# main-board_v1_3.net
KiCad netlist of a schematic drawn in EAGLE
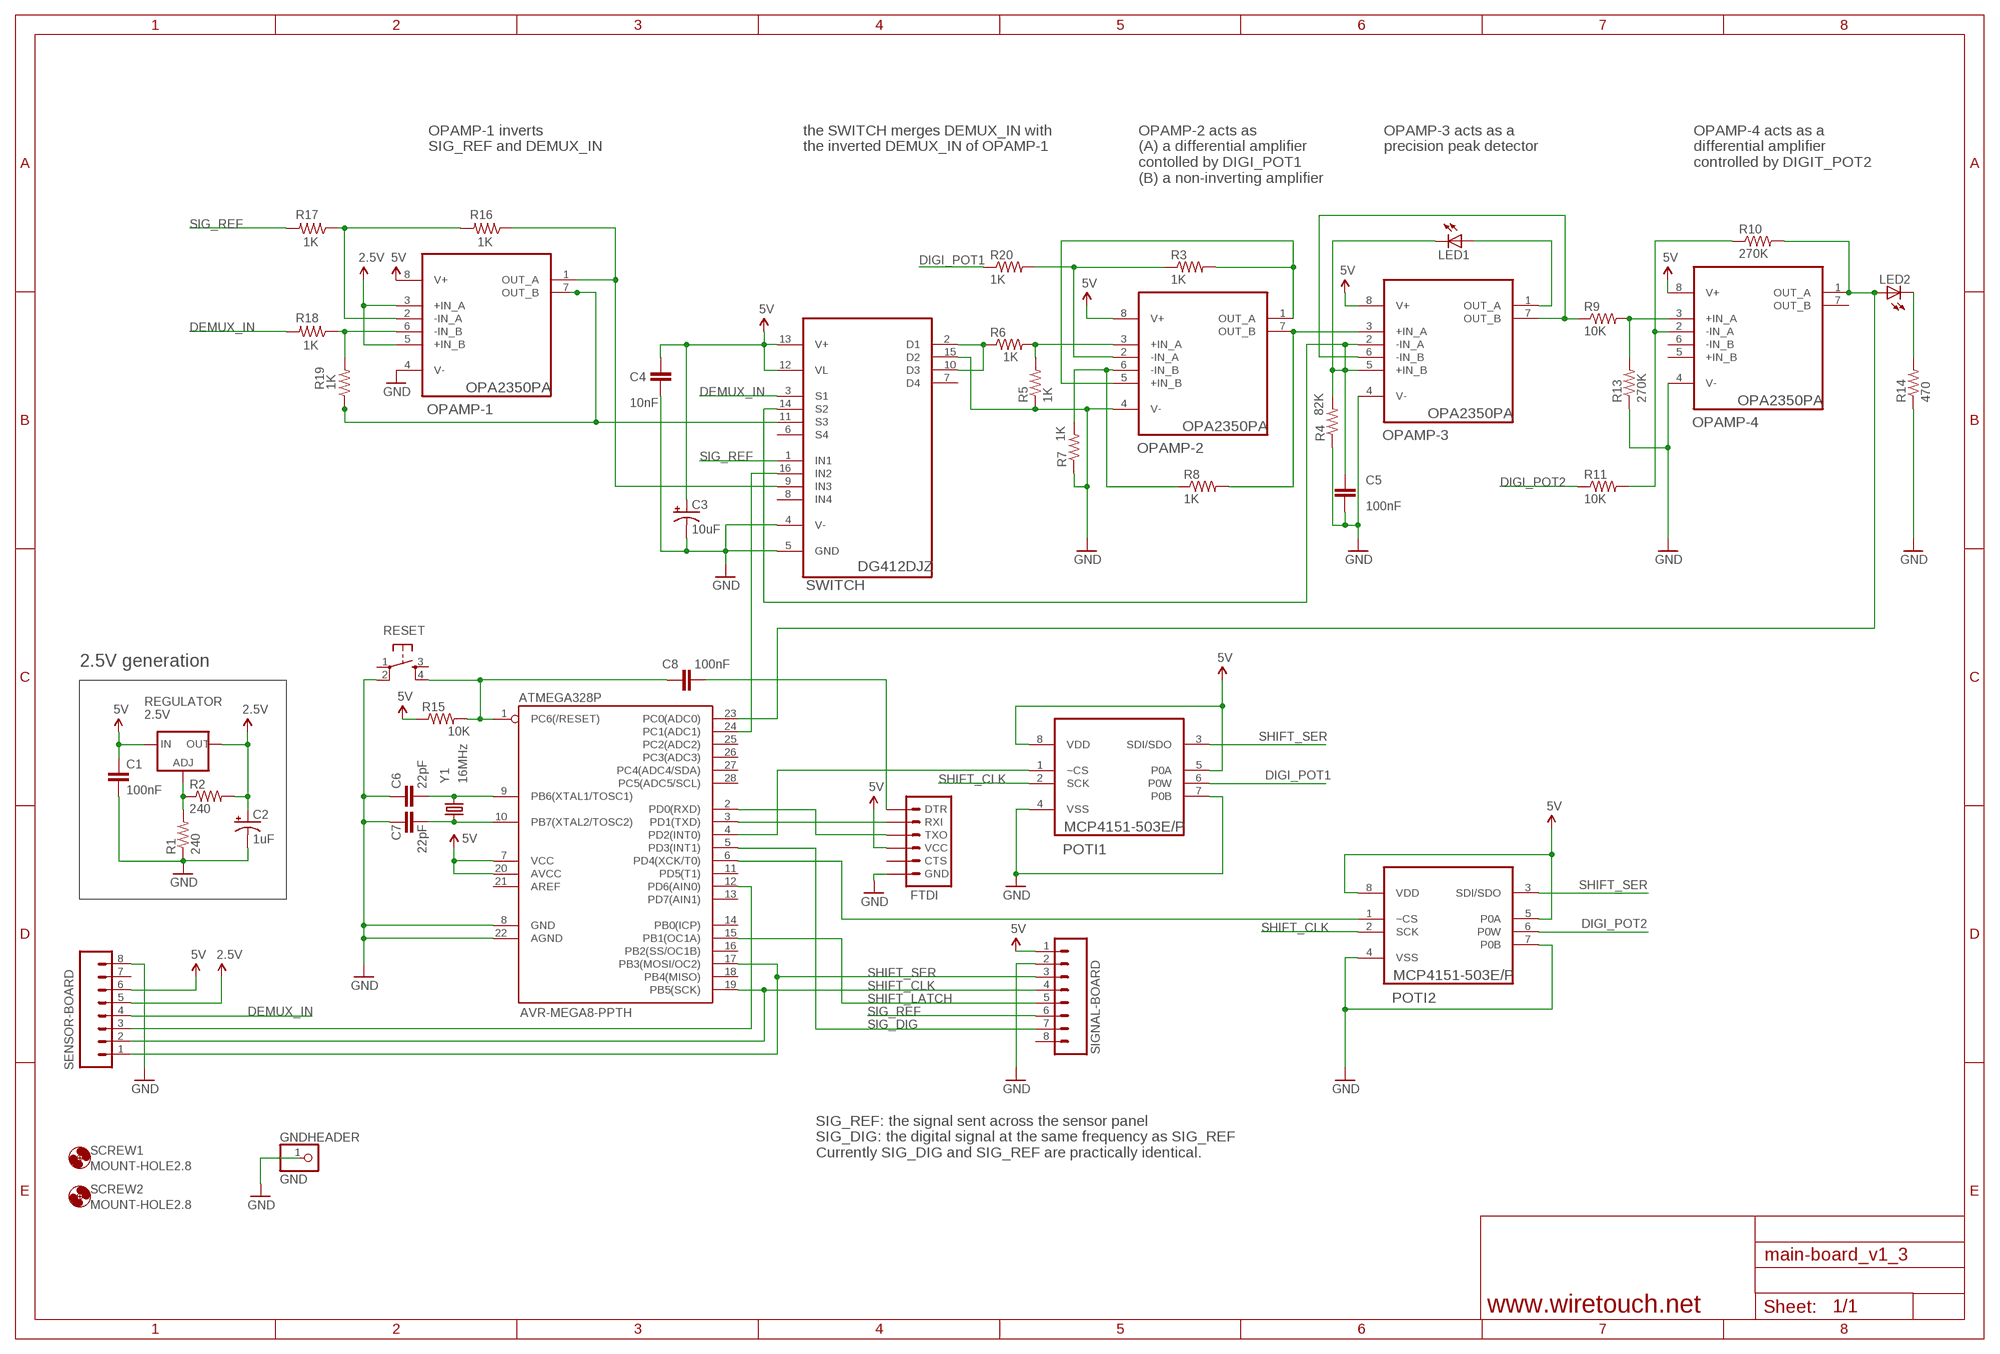
[diagram p0: schematic, sheet 1]

(export (version "E")
  (design (tool "Eeschema 10.0.6"))
  (components
    (comp (ref "ATMEGA328P")
      (value "AVR-MEGA8-PPTH")
      (footprint "eagle-import:DIL28-3")
      (libsource (lib "eagle-import") (part "AVR-MEGA8-PPTH"))
    )
    (comp (ref "C1")
      (value "100nF")
      (footprint "eagle-import:CAP-PTH-SMALL")
      (libsource (lib "eagle-import") (part "CAPPTH"))
    )
    (comp (ref "C2")
      (value "1uF")
      (footprint "eagle-import:CPOL-RADIAL-10UF-25V")
      (libsource (lib "eagle-import") (part "CAP_POLPTH2"))
    )
    (comp (ref "C3")
      (value "10uF")
      (footprint "eagle-import:CPOL-RADIAL-10UF-25V")
      (libsource (lib "eagle-import") (part "CAP_POLPTH2"))
    )
    (comp (ref "C4")
      (value "10nF")
      (footprint "eagle-import:CAP-PTH-SMALL")
      (libsource (lib "eagle-import") (part "CAPPTH"))
    )
    (comp (ref "C5")
      (value "100nF")
      (footprint "eagle-import:CAP-PTH-SMALL")
      (libsource (lib "eagle-import") (part "CAPPTH"))
    )
    (comp (ref "C6")
      (value "22pF")
      (footprint "eagle-import:CAP-PTH-SMALL2")
      (libsource (lib "eagle-import") (part "CAPPTH2"))
    )
    (comp (ref "C7")
      (value "22pF")
      (footprint "eagle-import:CAP-PTH-SMALL2")
      (libsource (lib "eagle-import") (part "CAPPTH2"))
    )
    (comp (ref "C8")
      (value "100nF")
      (footprint "eagle-import:CAP-PTH-SMALL2")
      (libsource (lib "eagle-import") (part "CAPPTH2"))
    )
    (comp (ref "FTDI")
      (value "ARDUINO_SERIAL_PROGRAMLONGPADS")
      (footprint "eagle-import:1X06_LONGPADS")
      (libsource (lib "eagle-import") (part "ARDUINO_SERIAL_PROGRAMLONGPADS"))
    )
    (comp (ref "GNDHEADER")
      (value "GND")
      (footprint "eagle-import:1X01")
      (libsource (lib "eagle-import") (part "PINHD-1X1"))
    )
    (comp (ref "LED1")
      (value "LED3MM")
      (footprint "eagle-import:LED3MM")
      (libsource (lib "eagle-import") (part "LED3MM"))
    )
    (comp (ref "LED2")
      (value "LED5MM")
      (footprint "eagle-import:LED5MM")
      (libsource (lib "eagle-import") (part "LED5MM"))
    )
    (comp (ref "OPAMP-1")
      (value "OPA2350PA")
      (footprint "eagle-import:DIP254P762X508-8")
      (libsource (lib "eagle-import") (part "OPA2350PA"))
    )
    (comp (ref "OPAMP-2")
      (value "OPA2350PA")
      (footprint "eagle-import:DIP254P762X508-8")
      (libsource (lib "eagle-import") (part "OPA2350PA"))
    )
    (comp (ref "OPAMP-3")
      (value "OPA2350PA")
      (footprint "eagle-import:DIP254P762X508-8")
      (libsource (lib "eagle-import") (part "OPA2350PA"))
    )
    (comp (ref "OPAMP-4")
      (value "OPA2350PA")
      (footprint "eagle-import:DIP254P762X508-8")
      (libsource (lib "eagle-import") (part "OPA2350PA"))
    )
    (comp (ref "POTI1")
      (value "MCP4151-503E/P")
      (footprint "eagle-import:DIP254P762X533-8")
      (libsource (lib "eagle-import") (part "MCP4151-503E/P"))
    )
    (comp (ref "POTI2")
      (value "MCP4151-503E/P")
      (footprint "eagle-import:DIP254P762X533-8")
      (libsource (lib "eagle-import") (part "MCP4151-503E/P"))
    )
    (comp (ref "R1")
      (value "240")
      (footprint "eagle-import:AXIAL-0.3")
      (libsource (lib "eagle-import") (part "RESISTORAXIAL-0.3"))
    )
    (comp (ref "R2")
      (value "240")
      (footprint "eagle-import:AXIAL-0.3")
      (libsource (lib "eagle-import") (part "RESISTORAXIAL-0.3"))
    )
    (comp (ref "R3")
      (value "1K")
      (footprint "eagle-import:AXIAL-0.3")
      (libsource (lib "eagle-import") (part "RESISTORAXIAL-0.3"))
    )
    (comp (ref "R4")
      (value "82K")
      (footprint "eagle-import:AXIAL-0.3")
      (libsource (lib "eagle-import") (part "RESISTORAXIAL-0.3"))
    )
    (comp (ref "R5")
      (value "1K")
      (footprint "eagle-import:AXIAL-0.3")
      (libsource (lib "eagle-import") (part "RESISTORAXIAL-0.3"))
    )
    (comp (ref "R6")
      (value "1K")
      (footprint "eagle-import:AXIAL-0.3")
      (libsource (lib "eagle-import") (part "RESISTORAXIAL-0.3"))
    )
    (comp (ref "R7")
      (value "1K")
      (footprint "eagle-import:AXIAL-0.3")
      (libsource (lib "eagle-import") (part "RESISTORAXIAL-0.3"))
    )
    (comp (ref "R8")
      (value "1K")
      (footprint "eagle-import:AXIAL-0.3")
      (libsource (lib "eagle-import") (part "RESISTORAXIAL-0.3"))
    )
    (comp (ref "R9")
      (value "10K")
      (footprint "eagle-import:AXIAL-0.3")
      (libsource (lib "eagle-import") (part "RESISTORAXIAL-0.3"))
    )
    (comp (ref "R10")
      (value "270K")
      (footprint "eagle-import:AXIAL-0.3")
      (libsource (lib "eagle-import") (part "RESISTORAXIAL-0.3"))
    )
    (comp (ref "R11")
      (value "10K")
      (footprint "eagle-import:AXIAL-0.3")
      (libsource (lib "eagle-import") (part "RESISTORAXIAL-0.3"))
    )
    (comp (ref "R13")
      (value "270K")
      (footprint "eagle-import:AXIAL-0.3")
      (libsource (lib "eagle-import") (part "RESISTORAXIAL-0.3"))
    )
    (comp (ref "R14")
      (value "470")
      (footprint "eagle-import:AXIAL-0.3")
      (libsource (lib "eagle-import") (part "RESISTORAXIAL-0.3"))
    )
    (comp (ref "R15")
      (value "10K")
      (footprint "eagle-import:AXIAL-0.3")
      (libsource (lib "eagle-import") (part "RESISTORAXIAL-0.3"))
    )
    (comp (ref "R16")
      (value "1K")
      (footprint "eagle-import:AXIAL-0.3")
      (libsource (lib "eagle-import") (part "RESISTORAXIAL-0.3"))
    )
    (comp (ref "R17")
      (value "1K")
      (footprint "eagle-import:AXIAL-0.3")
      (libsource (lib "eagle-import") (part "RESISTORAXIAL-0.3"))
    )
    (comp (ref "R18")
      (value "1K")
      (footprint "eagle-import:AXIAL-0.3")
      (libsource (lib "eagle-import") (part "RESISTORAXIAL-0.3"))
    )
    (comp (ref "R19")
      (value "1K")
      (footprint "eagle-import:AXIAL-0.3")
      (libsource (lib "eagle-import") (part "RESISTORAXIAL-0.3"))
    )
    (comp (ref "R20")
      (value "1K")
      (footprint "eagle-import:AXIAL-0.3")
      (libsource (lib "eagle-import") (part "RESISTORAXIAL-0.3"))
    )
    (comp (ref "REGULATOR")
      (value "2.5V")
      (footprint "eagle-import:TO220-ADJ")
      (libsource (lib "eagle-import") (part "V_REG_317SINK"))
    )
    (comp (ref "RESET")
      (value "Omron B3F momentary on switch")
      (footprint "eagle-import:TACTILE-PTH")
      (libsource (lib "eagle-import") (part "TAC_SWITCHPTH"))
    )
    (comp (ref "SCREW1")
      (value "MOUNT-HOLE2.8")
      (footprint "eagle-import:2,8")
      (libsource (lib "eagle-import") (part "MOUNT-HOLE2.8"))
    )
    (comp (ref "SCREW2")
      (value "MOUNT-HOLE2.8")
      (footprint "eagle-import:2,8")
      (libsource (lib "eagle-import") (part "MOUNT-HOLE2.8"))
    )
    (comp (ref "SENSOR-BOARD")
      (value "M08LONGPADS")
      (footprint "eagle-import:1X08_LONGPADS")
      (libsource (lib "eagle-import") (part "M08LONGPADS"))
    )
    (comp (ref "SIGNAL-BOARD")
      (value "M08LONGPADS")
      (footprint "eagle-import:1X08_LONGPADS")
      (libsource (lib "eagle-import") (part "M08LONGPADS"))
    )
    (comp (ref "SWITCH")
      (value "DG412DJZ")
      (footprint "eagle-import:DIP254P762X533-16")
      (libsource (lib "eagle-import") (part "DG412DJZ"))
    )
    (comp (ref "Y1")
      (value "16MHz")
      (footprint "eagle-import:HC49US")
      (libsource (lib "eagle-import") (part "CRYSTALHC49US"))
    )
  )
  (nets
    (net (code "1") (name "/DEMUX_IN") (class "Default")
      (node (ref "R18") (pin "P$2") (pinfunction "2_P$2") (pintype "passive"))
      (node (ref "SENSOR-BOARD") (pin "4") (pinfunction "4_4") (pintype "passive"))
      (node (ref "SWITCH") (pin "3") (pinfunction "S1_3") (pintype "input"))
    )
    (net (code "2") (name "/DIGI_POT1") (class "Default")
      (node (ref "POTI1") (pin "6") (pinfunction "P0W_6") (pintype "passive"))
      (node (ref "R20") (pin "P$1") (pinfunction "1_P$1") (pintype "passive"))
    )
    (net (code "3") (name "/DIGI_POT2") (class "Default")
      (node (ref "POTI2") (pin "6") (pinfunction "P0W_6") (pintype "passive"))
      (node (ref "R11") (pin "P$1") (pinfunction "1_P$1") (pintype "passive"))
    )
    (net (code "4") (name "/SHIFT_CLK") (class "Default")
      (node (ref "ATMEGA328P") (pin "19") (pinfunction "PB5(SCK)_19") (pintype "bidirectional"))
      (node (ref "POTI1") (pin "2") (pinfunction "SCK_2") (pintype "input"))
      (node (ref "POTI2") (pin "2") (pinfunction "SCK_2") (pintype "input"))
      (node (ref "SENSOR-BOARD") (pin "2") (pinfunction "2_2") (pintype "passive"))
      (node (ref "SIGNAL-BOARD") (pin "4") (pinfunction "4_4") (pintype "passive"))
    )
    (net (code "5") (name "/SHIFT_LATCH") (class "Default")
      (node (ref "ATMEGA328P") (pin "15") (pinfunction "PB1(OC1A)_15") (pintype "bidirectional"))
      (node (ref "SIGNAL-BOARD") (pin "5") (pinfunction "5_5") (pintype "passive"))
    )
    (net (code "6") (name "/SHIFT_SER") (class "Default")
      (node (ref "ATMEGA328P") (pin "17") (pinfunction "PB3(MOSI/OC2)_17") (pintype "bidirectional"))
      (node (ref "POTI1") (pin "3") (pinfunction "SDI/SDO_3") (pintype "bidirectional"))
      (node (ref "POTI2") (pin "3") (pinfunction "SDI/SDO_3") (pintype "bidirectional"))
      (node (ref "SENSOR-BOARD") (pin "1") (pinfunction "1_1") (pintype "passive"))
      (node (ref "SIGNAL-BOARD") (pin "3") (pinfunction "3_3") (pintype "passive"))
    )
    (net (code "7") (name "/SIG_DIG") (class "Default")
      (node (ref "ATMEGA328P") (pin "5") (pinfunction "PD3(INT1)_5") (pintype "bidirectional"))
      (node (ref "SIGNAL-BOARD") (pin "7") (pinfunction "7_7") (pintype "passive"))
    )
    (net (code "8") (name "/SIG_REF") (class "Default")
      (node (ref "R17") (pin "P$2") (pinfunction "2_P$2") (pintype "passive"))
      (node (ref "SIGNAL-BOARD") (pin "6") (pinfunction "6_6") (pintype "passive"))
      (node (ref "SWITCH") (pin "1") (pinfunction "IN1_1") (pintype "input"))
    )
    (net (code "9") (name "2.5V") (class "Default")
      (node (ref "C2") (pin "1") (pinfunction "+_1") (pintype "passive"))
      (node (ref "OPAMP-1") (pin "3") (pinfunction "+IN_A_3") (pintype "input"))
      (node (ref "OPAMP-1") (pin "5") (pinfunction "+IN_B_5") (pintype "input"))
      (node (ref "R2") (pin "P$2") (pinfunction "2_P$2") (pintype "passive"))
      (node (ref "REGULATOR") (pin "OUT") (pinfunction "OUT_OUT") (pintype "output"))
      (node (ref "SENSOR-BOARD") (pin "5") (pinfunction "5_5") (pintype "passive"))
    )
    (net (code "10") (name "5V") (class "Default")
      (node (ref "ATMEGA328P") (pin "20") (pinfunction "AVCC_20") (pintype "bidirectional"))
      (node (ref "ATMEGA328P") (pin "7") (pinfunction "VCC_7") (pintype "bidirectional"))
      (node (ref "C1") (pin "1") (pinfunction "1_1") (pintype "passive"))
      (node (ref "C3") (pin "1") (pinfunction "+_1") (pintype "passive"))
      (node (ref "C4") (pin "1") (pinfunction "1_1") (pintype "passive"))
      (node (ref "FTDI") (pin "4") (pinfunction "VCC_4") (pintype "passive"))
      (node (ref "OPAMP-1") (pin "8") (pinfunction "V+_8") (pintype "power_in"))
      (node (ref "OPAMP-2") (pin "8") (pinfunction "V+_8") (pintype "power_in"))
      (node (ref "OPAMP-3") (pin "8") (pinfunction "V+_8") (pintype "power_in"))
      (node (ref "OPAMP-4") (pin "8") (pinfunction "V+_8") (pintype "power_in"))
      (node (ref "POTI1") (pin "5") (pinfunction "P0A_5") (pintype "passive"))
      (node (ref "POTI1") (pin "8") (pinfunction "VDD_8") (pintype "power_in"))
      (node (ref "POTI2") (pin "5") (pinfunction "P0A_5") (pintype "passive"))
      (node (ref "POTI2") (pin "8") (pinfunction "VDD_8") (pintype "power_in"))
      (node (ref "R15") (pin "P$1") (pinfunction "1_P$1") (pintype "passive"))
      (node (ref "REGULATOR") (pin "IN") (pinfunction "IN_IN") (pintype "input"))
      (node (ref "SENSOR-BOARD") (pin "6") (pinfunction "6_6") (pintype "passive"))
      (node (ref "SIGNAL-BOARD") (pin "1") (pinfunction "1_1") (pintype "passive"))
      (node (ref "SWITCH") (pin "12") (pinfunction "VL_12") (pintype "power_in"))
      (node (ref "SWITCH") (pin "13") (pinfunction "V+_13") (pintype "power_in"))
    )
    (net (code "11") (name "GND") (class "Default")
      (node (ref "ATMEGA328P") (pin "22") (pinfunction "AGND_22") (pintype "bidirectional"))
      (node (ref "ATMEGA328P") (pin "8") (pinfunction "GND_8") (pintype "bidirectional"))
      (node (ref "C1") (pin "2") (pinfunction "2_2") (pintype "passive"))
      (node (ref "C2") (pin "2") (pinfunction "-_2") (pintype "passive"))
      (node (ref "C3") (pin "2") (pinfunction "-_2") (pintype "passive"))
      (node (ref "C4") (pin "2") (pinfunction "2_2") (pintype "passive"))
      (node (ref "C5") (pin "2") (pinfunction "2_2") (pintype "passive"))
      (node (ref "C6") (pin "1") (pinfunction "1_1") (pintype "passive"))
      (node (ref "C7") (pin "1") (pinfunction "1_1") (pintype "passive"))
      (node (ref "FTDI") (pin "6") (pinfunction "GND_6") (pintype "passive"))
      (node (ref "GNDHEADER") (pin "1") (pinfunction "1_1") (pintype "passive"))
      (node (ref "OPAMP-1") (pin "4") (pinfunction "V-_4") (pintype "power_in"))
      (node (ref "OPAMP-2") (pin "4") (pinfunction "V-_4") (pintype "power_in"))
      (node (ref "OPAMP-3") (pin "4") (pinfunction "V-_4") (pintype "power_in"))
      (node (ref "OPAMP-4") (pin "4") (pinfunction "V-_4") (pintype "power_in"))
      (node (ref "POTI1") (pin "4") (pinfunction "VSS_4") (pintype "power_in"))
      (node (ref "POTI1") (pin "7") (pinfunction "P0B_7") (pintype "passive"))
      (node (ref "POTI2") (pin "4") (pinfunction "VSS_4") (pintype "power_in"))
      (node (ref "POTI2") (pin "7") (pinfunction "P0B_7") (pintype "passive"))
      (node (ref "R1") (pin "P$1") (pinfunction "1_P$1") (pintype "passive"))
      (node (ref "R13") (pin "P$1") (pinfunction "1_P$1") (pintype "passive"))
      (node (ref "R14") (pin "P$1") (pinfunction "1_P$1") (pintype "passive"))
      (node (ref "R4") (pin "P$1") (pinfunction "1_P$1") (pintype "passive"))
      (node (ref "R5") (pin "P$1") (pinfunction "1_P$1") (pintype "passive"))
      (node (ref "R7") (pin "P$1") (pinfunction "1_P$1") (pintype "passive"))
      (node (ref "RESET") (pin "2") (pinfunction "2_2") (pintype "passive"))
      (node (ref "SENSOR-BOARD") (pin "8") (pinfunction "8_8") (pintype "passive"))
      (node (ref "SIGNAL-BOARD") (pin "2") (pinfunction "2_2") (pintype "passive"))
      (node (ref "SWITCH") (pin "15") (pinfunction "D2_15") (pintype "output"))
      (node (ref "SWITCH") (pin "4") (pinfunction "V-_4") (pintype "power_in"))
      (node (ref "SWITCH") (pin "5") (pinfunction "GND_5") (pintype "passive"))
    )
    (net (code "12") (name "Net-(ATMEGA328P-PB6(XTAL1{slash}TOSC1))") (class "Default")
      (node (ref "ATMEGA328P") (pin "9") (pinfunction "PB6(XTAL1/TOSC1)_9") (pintype "bidirectional"))
      (node (ref "C6") (pin "2") (pinfunction "2_2") (pintype "passive"))
      (node (ref "Y1") (pin "2") (pinfunction "2_2") (pintype "passive"))
    )
    (net (code "13") (name "Net-(ATMEGA328P-PB7(XTAL2{slash}TOSC2))") (class "Default")
      (node (ref "ATMEGA328P") (pin "10") (pinfunction "PB7(XTAL2/TOSC2)_10") (pintype "bidirectional"))
      (node (ref "C7") (pin "2") (pinfunction "2_2") (pintype "passive"))
      (node (ref "Y1") (pin "1") (pinfunction "1_1") (pintype "passive"))
    )
    (net (code "14") (name "Net-(ATMEGA328P-PC0(ADC0))") (class "Default")
      (node (ref "ATMEGA328P") (pin "23") (pinfunction "PC0(ADC0)_23") (pintype "bidirectional"))
      (node (ref "LED2") (pin "A") (pinfunction "A_A") (pintype "passive"))
      (node (ref "OPAMP-4") (pin "1") (pinfunction "OUT_A_1") (pintype "output"))
      (node (ref "R10") (pin "P$2") (pinfunction "2_P$2") (pintype "passive"))
    )
    (net (code "15") (name "Net-(ATMEGA328P-PC1(ADC1))") (class "Default")
      (node (ref "ATMEGA328P") (pin "24") (pinfunction "PC1(ADC1)_24") (pintype "bidirectional"))
      (node (ref "SWITCH") (pin "16") (pinfunction "IN2_16") (pintype "input"))
    )
    (net (code "16") (name "Net-(ATMEGA328P-PC6({slash}RESET))") (class "Default")
      (node (ref "ATMEGA328P") (pin "1") (pinfunction "PC6(/RESET)_1") (pintype "bidirectional"))
      (node (ref "C8") (pin "1") (pinfunction "1_1") (pintype "passive"))
      (node (ref "R15") (pin "P$2") (pinfunction "2_P$2") (pintype "passive"))
      (node (ref "RESET") (pin "4") (pinfunction "4_4") (pintype "passive"))
    )
    (net (code "17") (name "Net-(ATMEGA328P-PD0(RXD))") (class "Default")
      (node (ref "ATMEGA328P") (pin "2") (pinfunction "PD0(RXD)_2") (pintype "bidirectional"))
      (node (ref "FTDI") (pin "3") (pinfunction "TXO_3") (pintype "passive"))
    )
    (net (code "18") (name "Net-(ATMEGA328P-PD1(TXD))") (class "Default")
      (node (ref "ATMEGA328P") (pin "3") (pinfunction "PD1(TXD)_3") (pintype "bidirectional"))
      (node (ref "FTDI") (pin "2") (pinfunction "RXI_2") (pintype "passive"))
    )
    (net (code "19") (name "Net-(ATMEGA328P-PD2(INT0))") (class "Default")
      (node (ref "ATMEGA328P") (pin "4") (pinfunction "PD2(INT0)_4") (pintype "bidirectional"))
      (node (ref "POTI1") (pin "1") (pinfunction "~{CS}_1") (pintype "input"))
    )
    (net (code "20") (name "Net-(ATMEGA328P-PD4(XCK{slash}T0))") (class "Default")
      (node (ref "ATMEGA328P") (pin "6") (pinfunction "PD4(XCK/T0)_6") (pintype "bidirectional"))
      (node (ref "POTI2") (pin "1") (pinfunction "~{CS}_1") (pintype "input"))
    )
    (net (code "21") (name "Net-(ATMEGA328P-PD6(AIN0))") (class "Default")
      (node (ref "ATMEGA328P") (pin "12") (pinfunction "PD6(AIN0)_12") (pintype "bidirectional"))
      (node (ref "SENSOR-BOARD") (pin "3") (pinfunction "3_3") (pintype "passive"))
    )
    (net (code "22") (name "Net-(FTDI-DTR)") (class "Default")
      (node (ref "C8") (pin "2") (pinfunction "2_2") (pintype "passive"))
      (node (ref "FTDI") (pin "1") (pinfunction "DTR_1") (pintype "passive"))
    )
    (net (code "23") (name "Net-(LED1-C)") (class "Default")
      (node (ref "C5") (pin "1") (pinfunction "1_1") (pintype "passive"))
      (node (ref "LED1") (pin "K") (pinfunction "C_K") (pintype "passive"))
      (node (ref "OPAMP-3") (pin "2") (pinfunction "-IN_A_2") (pintype "input"))
      (node (ref "OPAMP-3") (pin "5") (pinfunction "+IN_B_5") (pintype "input"))
      (node (ref "R4") (pin "P$2") (pinfunction "2_P$2") (pintype "passive"))
      (node (ref "SWITCH") (pin "14") (pinfunction "S2_14") (pintype "input"))
    )
    (net (code "24") (name "Net-(LED2-C)") (class "Default")
      (node (ref "LED2") (pin "K") (pinfunction "C_K") (pintype "passive"))
      (node (ref "R14") (pin "P$2") (pinfunction "2_P$2") (pintype "passive"))
    )
    (net (code "25") (name "Net-(OPAMP-1--IN_A)") (class "Default")
      (node (ref "OPAMP-1") (pin "2") (pinfunction "-IN_A_2") (pintype "input"))
      (node (ref "R16") (pin "P$2") (pinfunction "2_P$2") (pintype "passive"))
      (node (ref "R17") (pin "P$1") (pinfunction "1_P$1") (pintype "passive"))
    )
    (net (code "26") (name "Net-(OPAMP-1--IN_B)") (class "Default")
      (node (ref "OPAMP-1") (pin "6") (pinfunction "-IN_B_6") (pintype "input"))
      (node (ref "R18") (pin "P$1") (pinfunction "1_P$1") (pintype "passive"))
      (node (ref "R19") (pin "P$2") (pinfunction "2_P$2") (pintype "passive"))
    )
    (net (code "27") (name "Net-(OPAMP-1-OUT_A)") (class "Default")
      (node (ref "OPAMP-1") (pin "1") (pinfunction "OUT_A_1") (pintype "output"))
      (node (ref "R16") (pin "P$1") (pinfunction "1_P$1") (pintype "passive"))
      (node (ref "SWITCH") (pin "9") (pinfunction "IN3_9") (pintype "input"))
    )
    (net (code "28") (name "Net-(OPAMP-1-OUT_B)") (class "Default")
      (node (ref "OPAMP-1") (pin "7") (pinfunction "OUT_B_7") (pintype "output"))
      (node (ref "R19") (pin "P$1") (pinfunction "1_P$1") (pintype "passive"))
      (node (ref "SWITCH") (pin "11") (pinfunction "S3_11") (pintype "input"))
    )
    (net (code "29") (name "Net-(OPAMP-2-+IN_A)") (class "Default")
      (node (ref "OPAMP-2") (pin "3") (pinfunction "+IN_A_3") (pintype "input"))
      (node (ref "R5") (pin "P$2") (pinfunction "2_P$2") (pintype "passive"))
      (node (ref "R6") (pin "P$2") (pinfunction "2_P$2") (pintype "passive"))
    )
    (net (code "30") (name "Net-(OPAMP-2-+IN_B)") (class "Default")
      (node (ref "OPAMP-2") (pin "1") (pinfunction "OUT_A_1") (pintype "output"))
      (node (ref "OPAMP-2") (pin "5") (pinfunction "+IN_B_5") (pintype "input"))
      (node (ref "R3") (pin "P$2") (pinfunction "2_P$2") (pintype "passive"))
    )
    (net (code "31") (name "Net-(OPAMP-2--IN_A)") (class "Default")
      (node (ref "OPAMP-2") (pin "2") (pinfunction "-IN_A_2") (pintype "input"))
      (node (ref "R20") (pin "P$2") (pinfunction "2_P$2") (pintype "passive"))
      (node (ref "R3") (pin "P$1") (pinfunction "1_P$1") (pintype "passive"))
    )
    (net (code "32") (name "Net-(OPAMP-2--IN_B)") (class "Default")
      (node (ref "OPAMP-2") (pin "6") (pinfunction "-IN_B_6") (pintype "input"))
      (node (ref "R7") (pin "P$2") (pinfunction "2_P$2") (pintype "passive"))
      (node (ref "R8") (pin "P$1") (pinfunction "1_P$1") (pintype "passive"))
    )
    (net (code "33") (name "Net-(OPAMP-2-OUT_B)") (class "Default")
      (node (ref "OPAMP-2") (pin "7") (pinfunction "OUT_B_7") (pintype "output"))
      (node (ref "OPAMP-3") (pin "3") (pinfunction "+IN_A_3") (pintype "input"))
      (node (ref "R8") (pin "P$2") (pinfunction "2_P$2") (pintype "passive"))
    )
    (net (code "34") (name "Net-(OPAMP-3--IN_B)") (class "Default")
      (node (ref "OPAMP-3") (pin "6") (pinfunction "-IN_B_6") (pintype "input"))
      (node (ref "OPAMP-3") (pin "7") (pinfunction "OUT_B_7") (pintype "output"))
      (node (ref "R9") (pin "P$1") (pinfunction "1_P$1") (pintype "passive"))
    )
    (net (code "35") (name "Net-(OPAMP-3-OUT_A)") (class "Default")
      (node (ref "LED1") (pin "A") (pinfunction "A_A") (pintype "passive"))
      (node (ref "OPAMP-3") (pin "1") (pinfunction "OUT_A_1") (pintype "output"))
    )
    (net (code "36") (name "Net-(OPAMP-4-+IN_A)") (class "Default")
      (node (ref "OPAMP-4") (pin "3") (pinfunction "+IN_A_3") (pintype "input"))
      (node (ref "R13") (pin "P$2") (pinfunction "2_P$2") (pintype "passive"))
      (node (ref "R9") (pin "P$2") (pinfunction "2_P$2") (pintype "passive"))
    )
    (net (code "37") (name "Net-(OPAMP-4--IN_A)") (class "Default")
      (node (ref "OPAMP-4") (pin "2") (pinfunction "-IN_A_2") (pintype "input"))
      (node (ref "R10") (pin "P$1") (pinfunction "1_P$1") (pintype "passive"))
      (node (ref "R11") (pin "P$2") (pinfunction "2_P$2") (pintype "passive"))
    )
    (net (code "38") (name "Net-(R1-2)") (class "Default")
      (node (ref "R1") (pin "P$2") (pinfunction "2_P$2") (pintype "passive"))
      (node (ref "R2") (pin "P$1") (pinfunction "1_P$1") (pintype "passive"))
      (node (ref "REGULATOR") (pin "ADJ") (pinfunction "ADJ_ADJ") (pintype "input"))
    )
    (net (code "39") (name "Net-(R6-1)") (class "Default")
      (node (ref "R6") (pin "P$1") (pinfunction "1_P$1") (pintype "passive"))
      (node (ref "SWITCH") (pin "10") (pinfunction "D3_10") (pintype "output"))
      (node (ref "SWITCH") (pin "2") (pinfunction "D1_2") (pintype "output"))
    )
    (net (code "40") (name "unconnected-(ATMEGA328P-AREF-Pad21)") (class "Default")
      (node (ref "ATMEGA328P") (pin "21") (pinfunction "AREF_21") (pintype "bidirectional"))
    )
    (net (code "41") (name "unconnected-(ATMEGA328P-PB0(ICP)-Pad14)") (class "Default")
      (node (ref "ATMEGA328P") (pin "14") (pinfunction "PB0(ICP)_14") (pintype "bidirectional"))
    )
    (net (code "42") (name "unconnected-(ATMEGA328P-PB2(SS{slash}OC1B)-Pad16)") (class "Default")
      (node (ref "ATMEGA328P") (pin "16") (pinfunction "PB2(SS/OC1B)_16") (pintype "bidirectional"))
    )
    (net (code "43") (name "unconnected-(ATMEGA328P-PB4(MISO)-Pad18)") (class "Default")
      (node (ref "ATMEGA328P") (pin "18") (pinfunction "PB4(MISO)_18") (pintype "bidirectional"))
    )
    (net (code "44") (name "unconnected-(ATMEGA328P-PC2(ADC2)-Pad25)") (class "Default")
      (node (ref "ATMEGA328P") (pin "25") (pinfunction "PC2(ADC2)_25") (pintype "bidirectional"))
    )
    (net (code "45") (name "unconnected-(ATMEGA328P-PC3(ADC3)-Pad26)") (class "Default")
      (node (ref "ATMEGA328P") (pin "26") (pinfunction "PC3(ADC3)_26") (pintype "bidirectional"))
    )
    (net (code "46") (name "unconnected-(ATMEGA328P-PC4(ADC4{slash}SDA)-Pad27)") (class "Default")
      (node (ref "ATMEGA328P") (pin "27") (pinfunction "PC4(ADC4/SDA)_27") (pintype "bidirectional"))
    )
    (net (code "47") (name "unconnected-(ATMEGA328P-PC5(ADC5{slash}SCL)-Pad28)") (class "Default")
      (node (ref "ATMEGA328P") (pin "28") (pinfunction "PC5(ADC5/SCL)_28") (pintype "bidirectional"))
    )
    (net (code "48") (name "unconnected-(ATMEGA328P-PD5(T1)-Pad11)") (class "Default")
      (node (ref "ATMEGA328P") (pin "11") (pinfunction "PD5(T1)_11") (pintype "bidirectional"))
    )
    (net (code "49") (name "unconnected-(ATMEGA328P-PD7(AIN1)-Pad13)") (class "Default")
      (node (ref "ATMEGA328P") (pin "13") (pinfunction "PD7(AIN1)_13") (pintype "bidirectional"))
    )
    (net (code "50") (name "unconnected-(FTDI-CTS-Pad5)") (class "Default")
      (node (ref "FTDI") (pin "5") (pinfunction "CTS_5") (pintype "passive"))
    )
    (net (code "51") (name "unconnected-(OPAMP-4-+IN_B-Pad5)") (class "Default")
      (node (ref "OPAMP-4") (pin "5") (pinfunction "+IN_B_5") (pintype "input"))
    )
    (net (code "52") (name "unconnected-(OPAMP-4--IN_B-Pad6)") (class "Default")
      (node (ref "OPAMP-4") (pin "6") (pinfunction "-IN_B_6") (pintype "input"))
    )
    (net (code "53") (name "unconnected-(OPAMP-4-OUT_B-Pad7)") (class "Default")
      (node (ref "OPAMP-4") (pin "7") (pinfunction "OUT_B_7") (pintype "output"))
    )
    (net (code "54") (name "unconnected-(RESET-Pad1)") (class "Default")
      (node (ref "RESET") (pin "1") (pinfunction "1_1") (pintype "passive"))
    )
    (net (code "55") (name "unconnected-(RESET-Pad3)") (class "Default")
      (node (ref "RESET") (pin "3") (pinfunction "3_3") (pintype "passive"))
    )
    (net (code "56") (name "unconnected-(SENSOR-BOARD-Pad7)") (class "Default")
      (node (ref "SENSOR-BOARD") (pin "7") (pinfunction "7_7") (pintype "passive"))
    )
    (net (code "57") (name "unconnected-(SIGNAL-BOARD-Pad8)") (class "Default")
      (node (ref "SIGNAL-BOARD") (pin "8") (pinfunction "8_8") (pintype "passive"))
    )
    (net (code "58") (name "unconnected-(SWITCH-D4-Pad7)") (class "Default")
      (node (ref "SWITCH") (pin "7") (pinfunction "D4_7") (pintype "output"))
    )
    (net (code "59") (name "unconnected-(SWITCH-IN4-Pad8)") (class "Default")
      (node (ref "SWITCH") (pin "8") (pinfunction "IN4_8") (pintype "input"))
    )
    (net (code "60") (name "unconnected-(SWITCH-S4-Pad6)") (class "Default")
      (node (ref "SWITCH") (pin "6") (pinfunction "S4_6") (pintype "input"))
    )
  )
)
